# Schematic_2023-04-19.net
KiCad netlist of a schematic drawn in Altium Designer
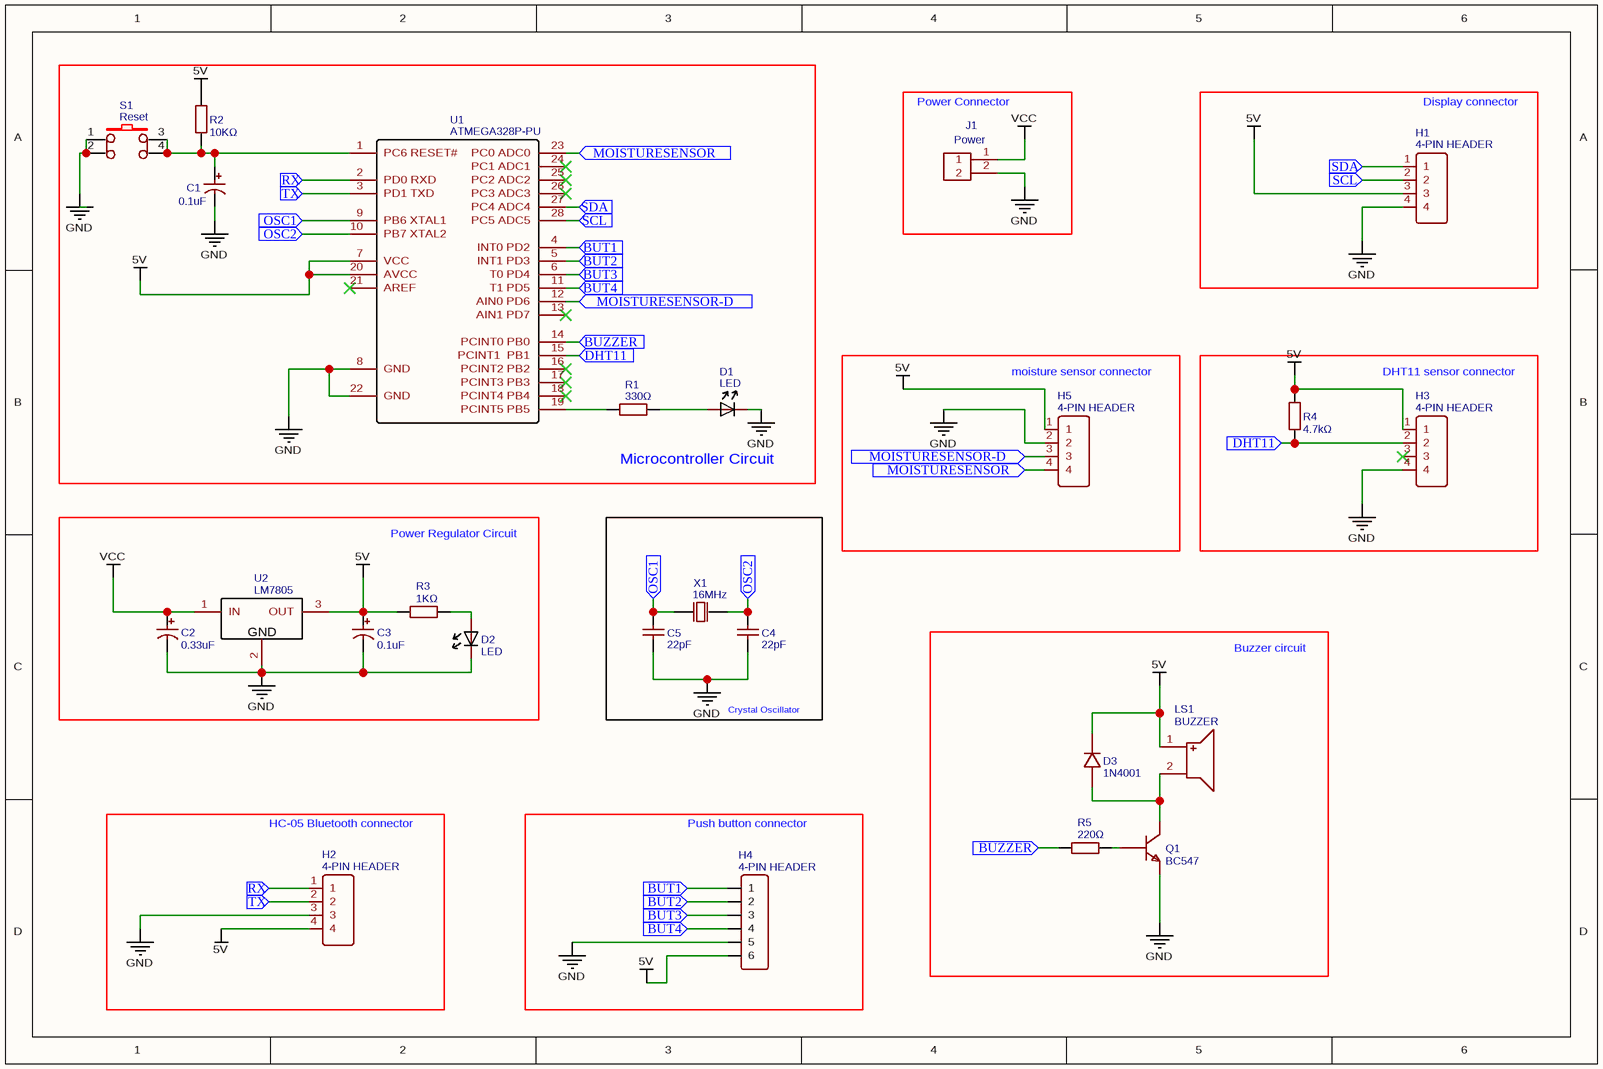
[diagram p0: Schematic_2023-04-19.schdoc]

(export (version "E")
  (design (tool "Eeschema 10.0.6"))
  (components
    (comp (ref "C1")
      (value "0.1uF")
      (fields (field (name "BOM_MANUFACTURER PART") "0.1UF 50V") (field (name "BOM_SUPPLIER PART") "C28061"))
      (libsource (lib "altium-import") (part "root_0_0.1uF_"))
    )
    (comp (ref "C2")
      (value "0.33uF")
      (fields
        (field (name "BOM_MANUFACTURER PART") "0.33uF 50V 5*11")
        (field (name "BOM_SUPPLIER PART") "C45097")
      )
      (libsource (lib "altium-import") (part "root_0_0.33uF_"))
    )
    (comp (ref "C3")
      (value "0.1uF")
      (fields (field (name "BOM_MANUFACTURER PART") "0.1UF 50V") (field (name "BOM_SUPPLIER PART") "C28061"))
      (libsource (lib "altium-import") (part "root_0_0.1uF_"))
    )
    (comp (ref "C4")
      (value "22pF")
      (fields
        (field (name "BOM_MANUFACTURER PART") "22pf/50V 10%")
        (field (name "BOM_SUPPLIER PART") "C9316")
      )
      (libsource (lib "altium-import") (part "root_3_22pF_"))
    )
    (comp (ref "C5")
      (value "22pF")
      (fields
        (field (name "BOM_MANUFACTURER PART") "22pf/50V 10%")
        (field (name "BOM_SUPPLIER PART") "C9316")
      )
      (libsource (lib "altium-import") (part "root_3_22pF_"))
    )
    (comp (ref "D1")
      (value "LED")
      (fields (field (name "BOM_MANUFACTURER PART") "5mm LED") (field (name "CONTRIBUTOR") "Axbri"))
      (libsource (lib "altium-import") (part "root_0_LED_"))
    )
    (comp (ref "D2")
      (value "LED")
      (fields (field (name "BOM_MANUFACTURER PART") "5mm LED") (field (name "CONTRIBUTOR") "Axbri"))
      (libsource (lib "altium-import") (part "root_3_LED_"))
    )
    (comp (ref "D3")
      (value "1N4001")
      (fields (field (name "BOM_SUPPLIER PART") "C99656") (field (name "CONTRIBUTOR") "LCSC"))
      (libsource (lib "altium-import") (part "root_3_1N4001_"))
    )
    (comp (ref "H1")
      (value "4-PIN HEADER")
      (fields (field (name "CONTRIBUTOR") "Kang Yi Te"))
      (libsource (lib "altium-import") (part "root_0_4-PIN HEADER_"))
    )
    (comp (ref "H2")
      (value "4-PIN HEADER")
      (fields (field (name "CONTRIBUTOR") "Kang Yi Te"))
      (libsource (lib "altium-import") (part "root_0_4-PIN HEADER_"))
    )
    (comp (ref "H3")
      (value "4-PIN HEADER")
      (fields (field (name "CONTRIBUTOR") "Kang Yi Te"))
      (libsource (lib "altium-import") (part "root_0_4-PIN HEADER_"))
    )
    (comp (ref "H4")
      (value "4-PIN HEADER")
      (fields (field (name "BOM_SUPPLIER PART") "C40877") (field (name "CONTRIBUTOR") "LCEDA_Lib"))
      (libsource (lib "") (part "root_0_4-PIN HEADER__1"))
    )
    (comp (ref "H5")
      (value "4-PIN HEADER")
      (fields (field (name "CONTRIBUTOR") "Kang Yi Te"))
      (libsource (lib "altium-import") (part "root_0_4-PIN HEADER_"))
    )
    (comp (ref "J1")
      (value "Power")
      (fields
        (field (name "BOM_MANUFACTURER PART") "XHB-2A Connector")
        (field (name "BOM_SUPPLIER PART") "C57981")
      )
      (libsource (lib "altium-import") (part "root_0_Power_"))
    )
    (comp (ref "LS1")
      (value "BUZZER")
      (fields
        (field (name "BOM_MANUFACTURER PART") "BUZZERHMB1206-03")
        (field (name "BOM_SUPPLIER PART") "C96101")
        (field (name "CONTRIBUTOR") "วริศรา เกรียงไกรวัฒน์ /ทิพพะ")
      )
      (libsource (lib "altium-import") (part "root_0_BUZZER_"))
    )
    (comp (ref "Q1")
      (value "BC547")
      (fields
        (field (name "BOM_SUPPLIER PART") "C900798")
        (field (name "BOM_MANUFACTURER PART") "BC547BTF")
        (field (name "CONTRIBUTOR") "LCSC")
      )
      (libsource (lib "altium-import") (part "root_0_BC547_"))
    )
    (comp (ref "R1")
      (value "330Ω")
      (fields
        (field (name "POWER") "1/4W")
        (field (name "TOLERANCE") "±1%")
        (field (name "BOM_SUPPLIER PART") "E57439")
      )
      (libsource (lib "altium-import") (part "root_0_330Ω_"))
    )
    (comp (ref "R2")
      (value "10KΩ")
      (fields
        (field (name "POWER") "1/4W")
        (field (name "TOLERANCE") "±1%")
        (field (name "BOM_SUPPLIER PART") "E57439")
      )
      (libsource (lib "altium-import") (part "root_3_10KΩ_"))
    )
    (comp (ref "R3")
      (value "1KΩ")
      (fields
        (field (name "POWER") "1/4W")
        (field (name "TOLERANCE") "±1%")
        (field (name "BOM_SUPPLIER PART") "E57439")
      )
      (libsource (lib "altium-import") (part "root_0_1KΩ_"))
    )
    (comp (ref "R4")
      (value "4.7kΩ")
      (fields
        (field (name "POWER") "1/4W")
        (field (name "TOLERANCE") "±1%")
        (field (name "BOM_SUPPLIER PART") "E57439")
      )
      (libsource (lib "altium-import") (part "root_3_4.7kΩ_"))
    )
    (comp (ref "R5")
      (value "220Ω")
      (fields
        (field (name "POWER") "1/4W")
        (field (name "TOLERANCE") "±1%")
        (field (name "BOM_SUPPLIER PART") "E57439")
      )
      (libsource (lib "altium-import") (part "root_0_220Ω_"))
    )
    (comp (ref "S1")
      (value "Reset")
      (fields
        (field (name "BOM_SUPPLIER PART") "C59980")
        (field (name "BOM_MANUFACTURER PART") "button6*6*8.5")
      )
      (libsource (lib "altium-import") (part "root_0_Reset_"))
    )
    (comp (ref "U1")
      (value "ATMEGA328P-PU")
      (fields (field (name "BOM_SUPPLIER PART") "C33901") (field (name "CONTRIBUTOR") "LCSC"))
      (libsource (lib "altium-import") (part "root_0_ATMEGA328P-PU_"))
    )
    (comp (ref "U2")
      (value "LM7805")
      (fields
        (field (name "BOM_MANUFACTURER PART") "L7805CV-DG")
        (field (name "BOM_SUPPLIER PART") "C3795")
        (field (name "CONTRIBUTOR") "LCEDA_Lib")
      )
      (libsource (lib "altium-import") (part "root_0_LM7805_"))
    )
    (comp (ref "X1")
      (value "16MHz")
      (fields
        (field (name "BOM_SUPPLIER PART") "C1669847")
        (field (name "BOM_MANUFACTURER PART") "ATS16A")
        (field (name "CONTRIBUTOR") "lcsc")
      )
      (libsource (lib "altium-import") (part "root_0_16MHz_"))
    )
  )
  (nets
    (net (code "1") (name "/BUT1") (class "Default")
      (node (ref "H4") (pin "1") (pinfunction "1_1") (pintype "passive"))
      (node (ref "U1") (pin "4") (pinfunction "INT0_PD2_4") (pintype "passive"))
    )
    (net (code "2") (name "/BUT2") (class "Default")
      (node (ref "H4") (pin "2") (pinfunction "2_2") (pintype "passive"))
      (node (ref "U1") (pin "5") (pinfunction "INT1_PD3_5") (pintype "passive"))
    )
    (net (code "3") (name "/BUT3") (class "Default")
      (node (ref "H4") (pin "3") (pinfunction "3_3") (pintype "passive"))
      (node (ref "U1") (pin "6") (pinfunction "T0_PD4_6") (pintype "passive"))
    )
    (net (code "4") (name "/BUT4") (class "Default")
      (node (ref "H4") (pin "4") (pinfunction "4_4") (pintype "passive"))
      (node (ref "U1") (pin "11") (pinfunction "T1_PD5_11") (pintype "passive"))
    )
    (net (code "5") (name "/BUZZER") (class "Default")
      (node (ref "R5") (pin "1") (pinfunction "1_1") (pintype "passive"))
      (node (ref "U1") (pin "14") (pinfunction "PCINT0_PB0_14") (pintype "passive"))
    )
    (net (code "6") (name "/DHT11") (class "Default")
      (node (ref "H3") (pin "2") (pinfunction "2_2") (pintype "passive"))
      (node (ref "R4") (pin "2") (pinfunction "2_2") (pintype "passive"))
      (node (ref "U1") (pin "15") (pinfunction "PCINT1__PB1_15") (pintype "passive"))
    )
    (net (code "7") (name "/MOISTURESENSOR") (class "Default")
      (node (ref "H5") (pin "4") (pinfunction "4_4") (pintype "passive"))
      (node (ref "U1") (pin "23") (pinfunction "PC0_ADC0_23") (pintype "passive"))
    )
    (net (code "8") (name "/MOISTURESENSOR-D") (class "Default")
      (node (ref "H5") (pin "3") (pinfunction "3_3") (pintype "passive"))
      (node (ref "U1") (pin "12") (pinfunction "AIN0_PD6_12") (pintype "passive"))
    )
    (net (code "9") (name "/OSC1") (class "Default")
      (node (ref "C5") (pin "1") (pinfunction "1_1") (pintype "passive"))
      (node (ref "U1") (pin "9") (pinfunction "PB6_XTAL1_9") (pintype "passive"))
      (node (ref "X1") (pin "1") (pinfunction "1_1") (pintype "passive"))
    )
    (net (code "10") (name "/OSC2") (class "Default")
      (node (ref "C4") (pin "1") (pinfunction "1_1") (pintype "passive"))
      (node (ref "U1") (pin "10") (pinfunction "PB7_XTAL2_10") (pintype "passive"))
      (node (ref "X1") (pin "2") (pinfunction "2_2") (pintype "passive"))
    )
    (net (code "11") (name "/RX") (class "Default")
      (node (ref "H2") (pin "1") (pinfunction "1_1") (pintype "passive"))
      (node (ref "U1") (pin "2") (pinfunction "PD0_RXD_2") (pintype "passive"))
    )
    (net (code "12") (name "/SCL") (class "Default")
      (node (ref "H1") (pin "2") (pinfunction "2_2") (pintype "passive"))
      (node (ref "U1") (pin "28") (pinfunction "PC5_ADC5_28") (pintype "passive"))
    )
    (net (code "13") (name "/SDA") (class "Default")
      (node (ref "H1") (pin "1") (pinfunction "1_1") (pintype "passive"))
      (node (ref "U1") (pin "27") (pinfunction "PC4_ADC4_27") (pintype "passive"))
    )
    (net (code "14") (name "/TX") (class "Default")
      (node (ref "H2") (pin "2") (pinfunction "2_2") (pintype "passive"))
      (node (ref "U1") (pin "3") (pinfunction "PD1_TXD_3") (pintype "passive"))
    )
    (net (code "15") (name "5V") (class "Default")
      (node (ref "C3") (pin "1") (pinfunction "1_1") (pintype "passive"))
      (node (ref "D3") (pin "1") (pinfunction "C_1") (pintype "passive"))
      (node (ref "H1") (pin "3") (pinfunction "3_3") (pintype "passive"))
      (node (ref "H2") (pin "4") (pinfunction "4_4") (pintype "passive"))
      (node (ref "H3") (pin "1") (pinfunction "1_1") (pintype "passive"))
      (node (ref "H4") (pin "6") (pinfunction "6_6") (pintype "passive"))
      (node (ref "H5") (pin "1") (pinfunction "1_1") (pintype "passive"))
      (node (ref "LS1") (pin "1") (pinfunction "1_1") (pintype "passive"))
      (node (ref "R2") (pin "1") (pinfunction "1_1") (pintype "passive"))
      (node (ref "R3") (pin "1") (pinfunction "1_1") (pintype "passive"))
      (node (ref "R4") (pin "1") (pinfunction "1_1") (pintype "passive"))
      (node (ref "U1") (pin "20") (pinfunction "AVCC_20") (pintype "passive"))
      (node (ref "U1") (pin "7") (pinfunction "VCC_7") (pintype "passive"))
      (node (ref "U2") (pin "3") (pinfunction "OUT_3") (pintype "passive"))
    )
    (net (code "16") (name "GND") (class "Default")
      (node (ref "C1") (pin "2") (pinfunction "2_2") (pintype "passive"))
      (node (ref "C2") (pin "2") (pinfunction "2_2") (pintype "passive"))
      (node (ref "C3") (pin "2") (pinfunction "2_2") (pintype "passive"))
      (node (ref "C4") (pin "2") (pinfunction "2_2") (pintype "passive"))
      (node (ref "C5") (pin "2") (pinfunction "2_2") (pintype "passive"))
      (node (ref "D1") (pin "2") (pinfunction "2_2") (pintype "passive"))
      (node (ref "D2") (pin "2") (pinfunction "2_2") (pintype "passive"))
      (node (ref "H1") (pin "4") (pinfunction "4_4") (pintype "passive"))
      (node (ref "H2") (pin "3") (pinfunction "3_3") (pintype "passive"))
      (node (ref "H3") (pin "4") (pinfunction "4_4") (pintype "passive"))
      (node (ref "H4") (pin "5") (pinfunction "5_5") (pintype "passive"))
      (node (ref "H5") (pin "2") (pinfunction "2_2") (pintype "passive"))
      (node (ref "J1") (pin "2") (pinfunction "2_2") (pintype "passive"))
      (node (ref "Q1") (pin "3") (pinfunction "E_3") (pintype "passive"))
      (node (ref "S1") (pin "1") (pinfunction "1_1") (pintype "passive"))
      (node (ref "S1") (pin "2") (pinfunction "2_2") (pintype "passive"))
      (node (ref "U1") (pin "22") (pinfunction "GND_22") (pintype "passive"))
      (node (ref "U1") (pin "8") (pinfunction "GND_8") (pintype "passive"))
      (node (ref "U2") (pin "2") (pinfunction "GND_2") (pintype "passive"))
    )
    (net (code "17") (name "Net-(D1-Pad1)") (class "Default")
      (node (ref "D1") (pin "1") (pinfunction "1_1") (pintype "passive"))
      (node (ref "R1") (pin "2") (pinfunction "2_2") (pintype "passive"))
    )
    (net (code "18") (name "Net-(D2-Pad1)") (class "Default")
      (node (ref "D2") (pin "1") (pinfunction "1_1") (pintype "passive"))
      (node (ref "R3") (pin "2") (pinfunction "2_2") (pintype "passive"))
    )
    (net (code "19") (name "Net-(D3-A)") (class "Default")
      (node (ref "D3") (pin "2") (pinfunction "A_2") (pintype "passive"))
      (node (ref "LS1") (pin "2") (pinfunction "2_2") (pintype "passive"))
      (node (ref "Q1") (pin "1") (pinfunction "C_1") (pintype "passive"))
    )
    (net (code "20") (name "Net-(Q1-B)") (class "Default")
      (node (ref "Q1") (pin "2") (pinfunction "B_2") (pintype "passive"))
      (node (ref "R5") (pin "2") (pinfunction "2_2") (pintype "passive"))
    )
    (net (code "21") (name "Net-(U1-PC6_RESET#)") (class "Default")
      (node (ref "C1") (pin "1") (pinfunction "1_1") (pintype "passive"))
      (node (ref "R2") (pin "2") (pinfunction "2_2") (pintype "passive"))
      (node (ref "S1") (pin "3") (pinfunction "3_3") (pintype "passive"))
      (node (ref "S1") (pin "4") (pinfunction "4_4") (pintype "passive"))
      (node (ref "U1") (pin "1") (pinfunction "PC6_RESET#_1") (pintype "passive"))
    )
    (net (code "22") (name "Net-(U1-PCINT5_PB5)") (class "Default")
      (node (ref "R1") (pin "1") (pinfunction "1_1") (pintype "passive"))
      (node (ref "U1") (pin "19") (pinfunction "PCINT5_PB5_19") (pintype "passive"))
    )
    (net (code "23") (name "VCC") (class "Default")
      (node (ref "C2") (pin "1") (pinfunction "1_1") (pintype "passive"))
      (node (ref "J1") (pin "1") (pinfunction "1_1") (pintype "passive"))
      (node (ref "U2") (pin "1") (pinfunction "IN_1") (pintype "passive"))
    )
    (net (code "24") (name "unconnected-(H3-Pad3)") (class "Default")
      (node (ref "H3") (pin "3") (pinfunction "3_3") (pintype "passive+no_connect"))
    )
    (net (code "25") (name "unconnected-(U1-AIN1_PD7-Pad13)") (class "Default")
      (node (ref "U1") (pin "13") (pinfunction "AIN1_PD7_13") (pintype "passive+no_connect"))
    )
    (net (code "26") (name "unconnected-(U1-AREF-Pad21)") (class "Default")
      (node (ref "U1") (pin "21") (pinfunction "AREF_21") (pintype "passive+no_connect"))
    )
    (net (code "27") (name "unconnected-(U1-PC1_ADC1-Pad24)") (class "Default")
      (node (ref "U1") (pin "24") (pinfunction "PC1_ADC1_24") (pintype "passive+no_connect"))
    )
    (net (code "28") (name "unconnected-(U1-PC2_ADC2-Pad25)") (class "Default")
      (node (ref "U1") (pin "25") (pinfunction "PC2_ADC2_25") (pintype "passive+no_connect"))
    )
    (net (code "29") (name "unconnected-(U1-PC3_ADC3-Pad26)") (class "Default")
      (node (ref "U1") (pin "26") (pinfunction "PC3_ADC3_26") (pintype "passive+no_connect"))
    )
    (net (code "30") (name "unconnected-(U1-PCINT2_PB2-Pad16)") (class "Default")
      (node (ref "U1") (pin "16") (pinfunction "PCINT2_PB2_16") (pintype "passive+no_connect"))
    )
    (net (code "31") (name "unconnected-(U1-PCINT3_PB3-Pad17)") (class "Default")
      (node (ref "U1") (pin "17") (pinfunction "PCINT3_PB3_17") (pintype "passive+no_connect"))
    )
    (net (code "32") (name "unconnected-(U1-PCINT4_PB4-Pad18)") (class "Default")
      (node (ref "U1") (pin "18") (pinfunction "PCINT4_PB4_18") (pintype "passive+no_connect"))
    )
  )
)
